# main.net
KiCad netlist of a schematic drawn in Altium Designer
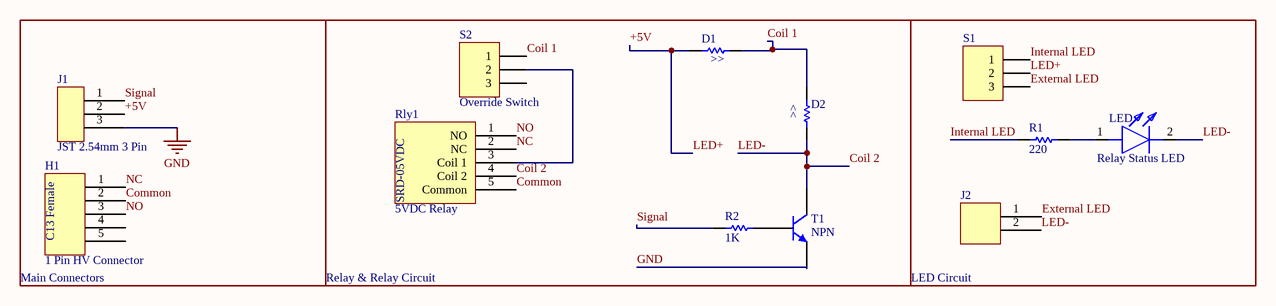
[diagram p0: main.SchDoc]

(export (version "E")
  (design (tool "Eeschema 10.0.6"))
  (components
    (comp (ref "D1")
      (value "Diode")
      (footprint "AXIAL-0.3")
      (description "Resistor")
      (fields (field (name "PUBLISHER") "Altium Limited"))
      (libsource (lib "Miscellaneous Devices") (part "Res1"))
    )
    (comp (ref "D2")
      (value "Diode")
      (footprint "AXIAL-0.3")
      (description "Resistor")
      (fields (field (name "PUBLISHER") "Altium Limited"))
      (libsource (lib "Miscellaneous Devices") (part "Res1"))
    )
    (comp (ref "H1")
      (value "1 Pin HV Connector")
      (footprint "C13 Female Plug")
      (description "Through-hole pad for soldering a high voltage wire")
      (libsource (lib "C13 surface mount female") (part "1 Pin HV Connector"))
    )
    (comp (ref "J1")
      (value "JST 2.54mm 3 Pin")
      (footprint "JST 2.54mm 3 pin")
      (libsource (lib "JST 2.54mm 3 Pin") (part "JST 2.54mm 3 Pin"))
    )
    (comp (ref "J2")
      (value "Component_1")
      (footprint "JST 2 pin 2.54mm")
      (libsource (lib "JST 2 pin 2.54mm") (part "Component_1"))
    )
    (comp (ref "LED")
      (value "~")
      (footprint "SamacSys:C5SMFRJECT0W0BB2")
      (description "LED")
      (fields
        (field (name "MANUFACTURER_PART_NUMBER") "C5SMF-RJE-CT0W0BB2")
        (field (name "MOUSER PART NUMBER") "941-C5SMFRJECT0W0BB2")
      )
      (libsource (lib "*") (part "C5SMF-RJE-CT0W0BB2"))
    )
    (comp (ref "R1")
      (value "220")
      (footprint "AXIAL-0.3")
      (description "Resistor")
      (fields (field (name "Comment") "Res1") (field (name "PUBLISHER") "Altium Limited"))
      (libsource (lib "Miscellaneous Devices") (part "Res1"))
    )
    (comp (ref "R2")
      (value "1K")
      (footprint "AXIAL-0.3")
      (description "Resistor")
      (fields (field (name "Comment") "Res1") (field (name "PUBLISHER") "Altium Limited"))
      (libsource (lib "Miscellaneous Devices") (part "Res1"))
    )
    (comp (ref "Rly1")
      (value "5VDC Relay")
      (footprint "SRD-05VDC Relay")
      (libsource (lib "SRD-05VDC Relay") (part "5VDC Relay"))
    )
    (comp (ref "S1")
      (value "Header 3")
      (footprint "HDR1X3")
      (description "Header, 3-Pin")
      (fields (field (name "PUBLISHER") "Altium Limited"))
      (libsource (lib "Miscellaneous Connectors") (part "Header 3"))
    )
    (comp (ref "S2")
      (value "Override Switch")
      (footprint "HDR1X3")
      (description "Header, 3-Pin")
      (fields (field (name "PUBLISHER") "Altium Limited"))
      (libsource (lib "Miscellaneous Connectors") (part "Header 3"))
    )
    (comp (ref "T1")
      (value "NPN")
      (footprint "TO-226-AA")
      (description "NPN Bipolar Transistor")
      (fields (field (name "PUBLISHER") "Altium Limited"))
      (libsource (lib "Miscellaneous Devices") (part "NPN"))
    )
  )
  (nets
    (net (code "1") (name "/+5V") (class "Default")
      (node (ref "D1") (pin "2") (pinfunction "2_2") (pintype "passive"))
      (node (ref "J1") (pin "2") (pintype "power_in"))
      (node (ref "S1") (pin "2") (pinfunction "2_2") (pintype "passive"))
    )
    (net (code "2") (name "/Coil 1") (class "Default")
      (node (ref "D1") (pin "1") (pinfunction "1_1") (pintype "passive"))
      (node (ref "D2") (pin "2") (pinfunction "2_2") (pintype "passive"))
      (node (ref "S2") (pin "1") (pinfunction "1_1") (pintype "passive"))
    )
    (net (code "3") (name "/Coil 2") (class "Default")
      (node (ref "D2") (pin "1") (pinfunction "1_1") (pintype "passive"))
      (node (ref "J2") (pin "2") (pintype "power_in"))
      (node (ref "LED") (pin "2") (pinfunction "K_2") (pintype "passive"))
      (node (ref "Rly1") (pin "4") (pinfunction "Coil_2_4") (pintype "power_in"))
      (node (ref "T1") (pin "1") (pinfunction "C_1") (pintype "passive"))
    )
    (net (code "4") (name "/Common") (class "Default")
      (node (ref "H1") (pin "2") (pintype "power_in"))
      (node (ref "Rly1") (pin "5") (pinfunction "Common_5") (pintype "power_in"))
    )
    (net (code "5") (name "/External LED") (class "Default")
      (node (ref "J2") (pin "1") (pintype "power_in"))
      (node (ref "S1") (pin "3") (pinfunction "3_3") (pintype "passive"))
    )
    (net (code "6") (name "/Internal LED") (class "Default")
      (node (ref "R1") (pin "2") (pinfunction "2_2") (pintype "passive"))
      (node (ref "S1") (pin "1") (pinfunction "1_1") (pintype "passive"))
    )
    (net (code "7") (name "/NC") (class "Default")
      (node (ref "H1") (pin "1") (pintype "power_in"))
      (node (ref "Rly1") (pin "2") (pinfunction "NC_2") (pintype "power_in"))
    )
    (net (code "8") (name "/NO") (class "Default")
      (node (ref "H1") (pin "3") (pintype "power_in"))
      (node (ref "Rly1") (pin "1") (pinfunction "NO_1") (pintype "power_in"))
    )
    (net (code "9") (name "/Signal") (class "Default")
      (node (ref "J1") (pin "1") (pintype "power_in"))
      (node (ref "R2") (pin "2") (pinfunction "2_2") (pintype "passive"))
    )
    (net (code "10") (name "GND") (class "Default")
      (node (ref "J1") (pin "3") (pintype "power_in"))
      (node (ref "T1") (pin "3") (pinfunction "E_3") (pintype "passive"))
    )
    (net (code "11") (name "Net-(LED-A)") (class "Default")
      (node (ref "LED") (pin "1") (pinfunction "A_1") (pintype "passive"))
      (node (ref "R1") (pin "1") (pinfunction "1_1") (pintype "passive"))
    )
    (net (code "12") (name "Net-(Rly1-Coil_1)") (class "Default")
      (node (ref "Rly1") (pin "3") (pinfunction "Coil_1_3") (pintype "power_in"))
      (node (ref "S2") (pin "2") (pinfunction "2_2") (pintype "passive"))
    )
    (net (code "13") (name "Net-(T1-B)") (class "Default")
      (node (ref "R2") (pin "1") (pinfunction "1_1") (pintype "passive"))
      (node (ref "T1") (pin "2") (pinfunction "B_2") (pintype "passive"))
    )
    (net (code "14") (name "unconnected-(H1-Pad4)") (class "Default")
      (node (ref "H1") (pin "4") (pintype "power_in"))
    )
    (net (code "15") (name "unconnected-(H1-Pad5)") (class "Default")
      (node (ref "H1") (pin "5") (pintype "power_in"))
    )
    (net (code "16") (name "unconnected-(S2-Pad3)") (class "Default")
      (node (ref "S2") (pin "3") (pinfunction "3_3") (pintype "passive"))
    )
  )
)
